# MIN-PCIE.net
KiCad netlist of a schematic drawn in Altium Designer
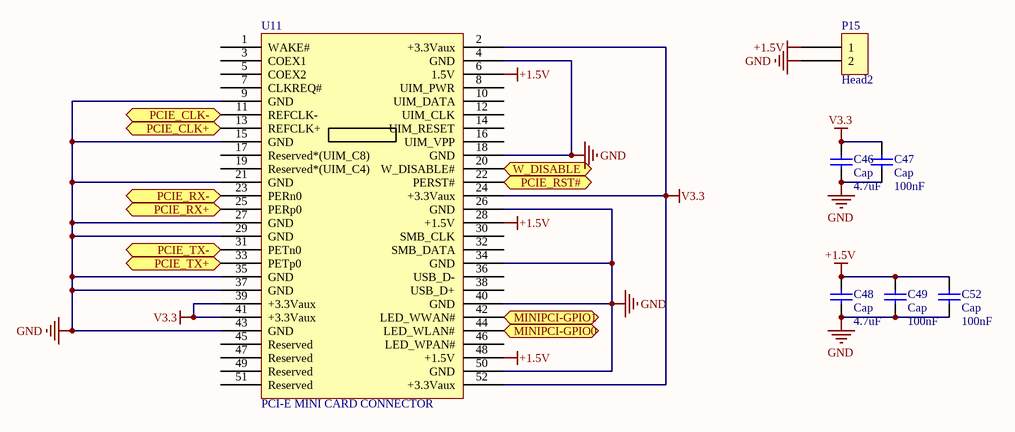
[diagram p0: MIN-PCIE.SchDoc]

(export (version "E")
  (design (tool "Eeschema 10.0.6"))
  (components
    (comp (ref "C46")
      (value "Cap")
      (footprint "R0603N")
      (description "Capacitor")
      (fields (field (name "ALTIUM_VALUE") "4.7uF") (field (name "PUBLISHER") "Altium Limited"))
      (libsource (lib "Miscellaneous Devices") (part "Cap"))
    )
    (comp (ref "C47")
      (value "Cap")
      (footprint "R0603N")
      (description "Capacitor")
      (fields (field (name "ALTIUM_VALUE") "100nF") (field (name "PUBLISHER") "Altium Limited"))
      (libsource (lib "Miscellaneous Devices") (part "Cap"))
    )
    (comp (ref "C48")
      (value "Cap")
      (footprint "R0603N")
      (description "Capacitor")
      (fields (field (name "ALTIUM_VALUE") "4.7uF") (field (name "PUBLISHER") "Altium Limited"))
      (libsource (lib "Miscellaneous Devices") (part "Cap"))
    )
    (comp (ref "C49")
      (value "Cap")
      (footprint "R0603N")
      (description "Capacitor")
      (fields (field (name "ALTIUM_VALUE") "100nF") (field (name "PUBLISHER") "Altium Limited"))
      (libsource (lib "Miscellaneous Devices") (part "Cap"))
    )
    (comp (ref "C52")
      (value "Cap")
      (footprint "R0603N")
      (description "Capacitor")
      (fields (field (name "ALTIUM_VALUE") "100nF") (field (name "PUBLISHER") "Altium Limited"))
      (libsource (lib "Miscellaneous Devices") (part "Cap"))
    )
    (comp (ref "P15") (value "Head2") (footprint "HDR1X2") (libsource (lib "Interface") (part "Head2")))
    (comp (ref "U11")
      (value "PCI-E MINI CARD CONNECTOR")
      (footprint "MC2716")
      (libsource (lib "Interface") (part "PCI-E MINI CARD CONNECTOR"))
    )
  )
  (nets
    (net (code "1") (name "+1.5V") (class "Default")
      (node (ref "C48") (pin "2") (pinfunction "2_2") (pintype "passive"))
      (node (ref "C49") (pin "2") (pinfunction "2_2") (pintype "passive"))
      (node (ref "C52") (pin "2") (pinfunction "2_2") (pintype "passive"))
      (node (ref "P15") (pin "1") (pinfunction "1_1") (pintype "passive"))
      (node (ref "U11") (pin "28") (pinfunction "+1.5V_28") (pintype "passive"))
      (node (ref "U11") (pin "48") (pinfunction "+1.5V_48") (pintype "passive"))
      (node (ref "U11") (pin "6") (pinfunction "1.5V_6") (pintype "passive"))
    )
    (net (code "2") (name "/MINIPCI-GPIO0") (class "Default")
      (node (ref "U11") (pin "44") (pinfunction "LED_WLAN#_44") (pintype "passive"))
    )
    (net (code "3") (name "/MINIPCI-GPIO1") (class "Default")
      (node (ref "U11") (pin "42") (pinfunction "LED_WWAN#_42") (pintype "passive"))
    )
    (net (code "4") (name "/PCIE_CLK+") (class "Default")
      (node (ref "U11") (pin "13") (pinfunction "REFCLK+_13") (pintype "passive"))
    )
    (net (code "5") (name "/PCIE_CLK-") (class "Default")
      (node (ref "U11") (pin "11") (pinfunction "REFCLK-_11") (pintype "passive"))
    )
    (net (code "6") (name "/PCIE_RST#") (class "Default")
      (node (ref "U11") (pin "22") (pinfunction "PERST#_22") (pintype "passive"))
    )
    (net (code "7") (name "/PCIE_RX+") (class "Default")
      (node (ref "U11") (pin "25") (pinfunction "PERp0_25") (pintype "passive"))
    )
    (net (code "8") (name "/PCIE_RX-") (class "Default")
      (node (ref "U11") (pin "23") (pinfunction "PERn0_23") (pintype "passive"))
    )
    (net (code "9") (name "/PCIE_TX+") (class "Default")
      (node (ref "U11") (pin "33") (pinfunction "PETp0_33") (pintype "passive"))
    )
    (net (code "10") (name "/PCIE_TX-") (class "Default")
      (node (ref "U11") (pin "31") (pinfunction "PETn0_31") (pintype "passive"))
    )
    (net (code "11") (name "/W_DISABLE") (class "Default")
      (node (ref "U11") (pin "20") (pinfunction "W_DISABLE#_20") (pintype "passive"))
    )
    (net (code "12") (name "GND") (class "Default")
      (node (ref "C46") (pin "1") (pinfunction "1_1") (pintype "passive"))
      (node (ref "C47") (pin "1") (pinfunction "1_1") (pintype "passive"))
      (node (ref "C48") (pin "1") (pinfunction "1_1") (pintype "passive"))
      (node (ref "C49") (pin "1") (pinfunction "1_1") (pintype "passive"))
      (node (ref "C52") (pin "1") (pinfunction "1_1") (pintype "passive"))
      (node (ref "P15") (pin "2") (pinfunction "2_2") (pintype "passive"))
      (node (ref "U11") (pin "15") (pinfunction "GND_15") (pintype "passive"))
      (node (ref "U11") (pin "18") (pinfunction "GND_18") (pintype "passive"))
      (node (ref "U11") (pin "21") (pinfunction "GND_21") (pintype "passive"))
      (node (ref "U11") (pin "26") (pinfunction "GND_26") (pintype "passive"))
      (node (ref "U11") (pin "27") (pinfunction "GND_27") (pintype "passive"))
      (node (ref "U11") (pin "29") (pinfunction "GND_29") (pintype "passive"))
      (node (ref "U11") (pin "34") (pinfunction "GND_34") (pintype "passive"))
      (node (ref "U11") (pin "35") (pinfunction "GND_35") (pintype "passive"))
      (node (ref "U11") (pin "37") (pinfunction "GND_37") (pintype "passive"))
      (node (ref "U11") (pin "4") (pinfunction "GND_4") (pintype "passive"))
      (node (ref "U11") (pin "40") (pinfunction "GND_40") (pintype "passive"))
      (node (ref "U11") (pin "43") (pinfunction "GND_43") (pintype "passive"))
      (node (ref "U11") (pin "50") (pinfunction "GND_50") (pintype "passive"))
      (node (ref "U11") (pin "9") (pinfunction "GND_9") (pintype "passive"))
    )
    (net (code "13") (name "V3.3") (class "Default")
      (node (ref "C46") (pin "2") (pinfunction "2_2") (pintype "passive"))
      (node (ref "C47") (pin "2") (pinfunction "2_2") (pintype "passive"))
      (node (ref "U11") (pin "2") (pinfunction "+3.3Vaux_2") (pintype "passive"))
      (node (ref "U11") (pin "24") (pinfunction "+3.3Vaux_24") (pintype "passive"))
      (node (ref "U11") (pin "39") (pinfunction "+3.3Vaux_39") (pintype "passive"))
      (node (ref "U11") (pin "41") (pinfunction "+3.3Vaux_41") (pintype "passive"))
      (node (ref "U11") (pin "52") (pinfunction "+3.3Vaux_52") (pintype "passive"))
    )
    (net (code "14") (name "unconnected-(U11-CLKREQ#-Pad7)") (class "Default")
      (node (ref "U11") (pin "7") (pinfunction "CLKREQ#_7") (pintype "passive"))
    )
    (net (code "15") (name "unconnected-(U11-COEX1-Pad3)") (class "Default")
      (node (ref "U11") (pin "3") (pinfunction "COEX1_3") (pintype "passive"))
    )
    (net (code "16") (name "unconnected-(U11-COEX2-Pad5)") (class "Default")
      (node (ref "U11") (pin "5") (pinfunction "COEX2_5") (pintype "passive"))
    )
    (net (code "17") (name "unconnected-(U11-LED_WPAN#-Pad46)") (class "Default")
      (node (ref "U11") (pin "46") (pinfunction "LED_WPAN#_46") (pintype "passive"))
    )
    (net (code "18") (name "unconnected-(U11-Reserved*(UIM_C4)-Pad19)") (class "Default")
      (node (ref "U11") (pin "19") (pinfunction "Reserved*(UIM_C4)_19") (pintype "passive"))
    )
    (net (code "19") (name "unconnected-(U11-Reserved*(UIM_C8)-Pad17)") (class "Default")
      (node (ref "U11") (pin "17") (pinfunction "Reserved*(UIM_C8)_17") (pintype "passive"))
    )
    (net (code "20") (name "unconnected-(U11-Reserved-Pad45)") (class "Default")
      (node (ref "U11") (pin "45") (pinfunction "Reserved_45") (pintype "passive"))
    )
    (net (code "21") (name "unconnected-(U11-Reserved-Pad47)") (class "Default")
      (node (ref "U11") (pin "47") (pinfunction "Reserved_47") (pintype "passive"))
    )
    (net (code "22") (name "unconnected-(U11-Reserved-Pad49)") (class "Default")
      (node (ref "U11") (pin "49") (pinfunction "Reserved_49") (pintype "passive"))
    )
    (net (code "23") (name "unconnected-(U11-Reserved-Pad51)") (class "Default")
      (node (ref "U11") (pin "51") (pinfunction "Reserved_51") (pintype "passive"))
    )
    (net (code "24") (name "unconnected-(U11-SMB_CLK-Pad30)") (class "Default")
      (node (ref "U11") (pin "30") (pinfunction "SMB_CLK_30") (pintype "passive"))
    )
    (net (code "25") (name "unconnected-(U11-SMB_DATA-Pad32)") (class "Default")
      (node (ref "U11") (pin "32") (pinfunction "SMB_DATA_32") (pintype "passive"))
    )
    (net (code "26") (name "unconnected-(U11-UIM_CLK-Pad12)") (class "Default")
      (node (ref "U11") (pin "12") (pinfunction "UIM_CLK_12") (pintype "passive"))
    )
    (net (code "27") (name "unconnected-(U11-UIM_DATA-Pad10)") (class "Default")
      (node (ref "U11") (pin "10") (pinfunction "UIM_DATA_10") (pintype "passive"))
    )
    (net (code "28") (name "unconnected-(U11-UIM_PWR-Pad8)") (class "Default")
      (node (ref "U11") (pin "8") (pinfunction "UIM_PWR_8") (pintype "passive"))
    )
    (net (code "29") (name "unconnected-(U11-UIM_RESET-Pad14)") (class "Default")
      (node (ref "U11") (pin "14") (pinfunction "UIM_RESET_14") (pintype "passive"))
    )
    (net (code "30") (name "unconnected-(U11-UIM_VPP-Pad16)") (class "Default")
      (node (ref "U11") (pin "16") (pinfunction "UIM_VPP_16") (pintype "passive"))
    )
    (net (code "31") (name "unconnected-(U11-USB_D+-Pad38)") (class "Default")
      (node (ref "U11") (pin "38") (pinfunction "USB_D+_38") (pintype "passive"))
    )
    (net (code "32") (name "unconnected-(U11-USB_D--Pad36)") (class "Default")
      (node (ref "U11") (pin "36") (pinfunction "USB_D-_36") (pintype "passive"))
    )
    (net (code "33") (name "unconnected-(U11-WAKE#-Pad1)") (class "Default")
      (node (ref "U11") (pin "1") (pinfunction "WAKE#_1") (pintype "passive"))
    )
  )
)
